# TOP.net
KiCad netlist of a schematic drawn in Altium Designer
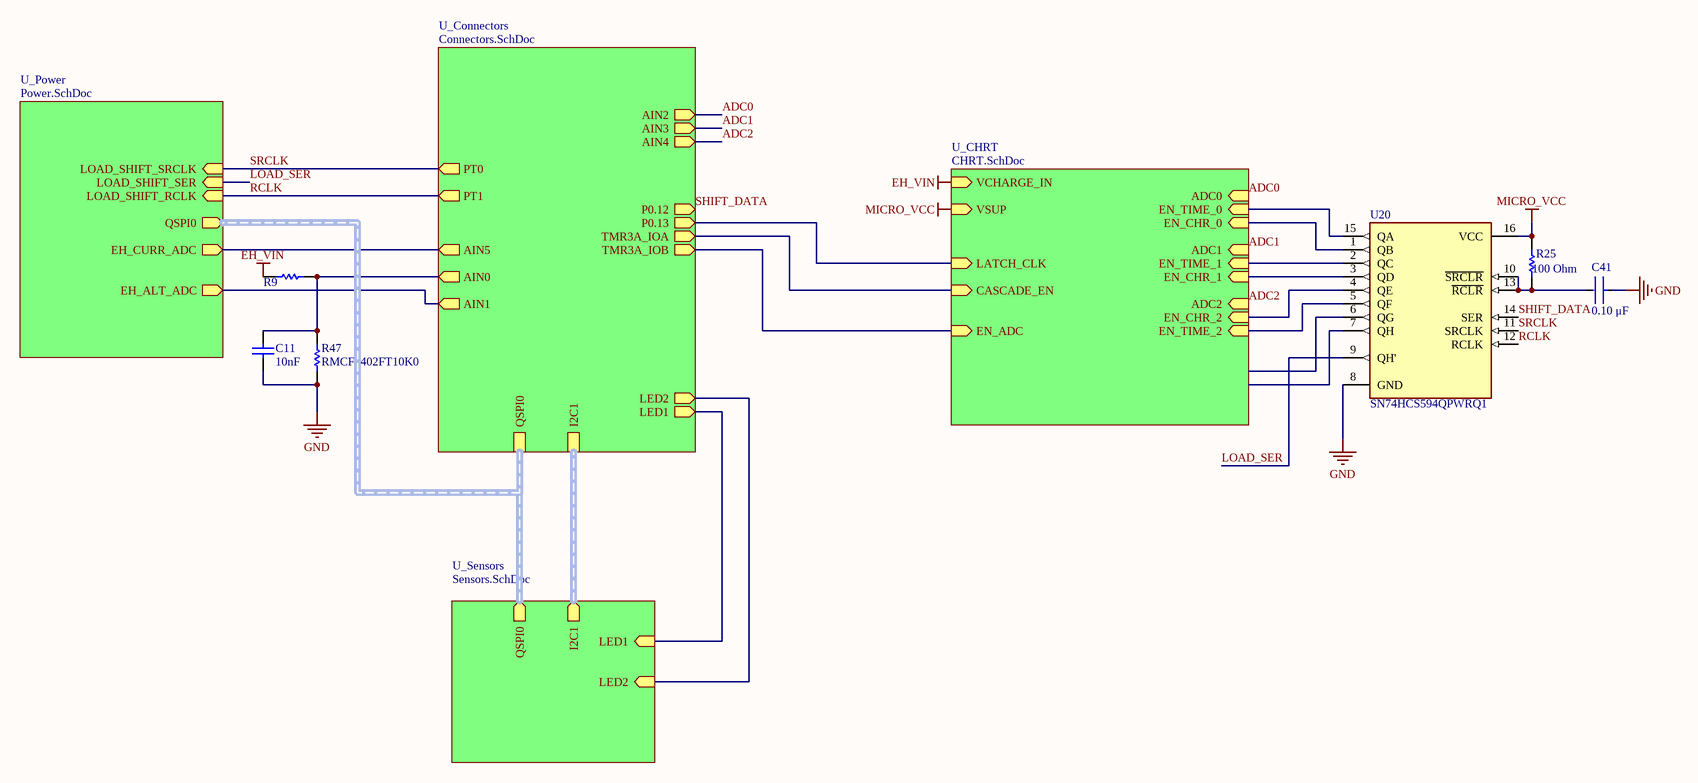
[diagram p0: TOP.SchDoc]

(export (version "E")
  (design (tool "Eeschema 10.0.6"))
  (components
    (comp (ref "C11")
      (value "GRM188R71H103KA01D")
      (footprint "CAPC1608X90X35ML10T15")
      (description "Chip Capacitor, 10 nF, +/- 10%, 50 V, -55 to 125 degC, 0603 (1608 Metric), RoHS, Tape and Reel")
      (fields
        (field (name "VOLTAGE") "50V")
        (field (name "TOLERANCE") "10%")
        (field (name "CAPACITANCE") "10nF")
      )
      (libsource (lib "Altium Content Vault") (part "CAP-NP-2"))
    )
    (comp (ref "C41")
      (value "C0402C104K8PACTU")
      (footprint "FP-C0402-BB-MFG")
      (description "CAP CER 0.1UF 10V X5R 0402")
      (fields
        (field (name "CAPACITANCE") "0.10 μF")
        (field (name "MANUFACTURER") "Kemet")
        (field (name "TOLERANCE") "0.1")
      )
      (libsource (lib "Altium Content Vault") (part "b4654b650e69147ec39a6b967a45e02"))
    )
    (comp (ref "R9")
      (value "RC0402JR-075M6L")
      (footprint "RESC1005X40X25ML05T10")
      (fields (field (name "MANUFACTURER") "Yageo / Phycomp"))
      (libsource (lib "Altium Content Vault") (part "RES"))
    )
    (comp (ref "R25")
      (value "ERJ-2RKF1000X")
      (footprint "RESC1005X40X25LL05T05")
      (description "Chip Resistor, 100 Ohm, +/- 1%, 100 mW, -55 to 155 degC, 0402 (1005 Metric), RoHS, Tape and Reel")
      (fields
        (field (name "MANUFACTURER") "Basic Passives")
        (field (name "TOLERANCE") "1%")
        (field (name "RESISTANCE") "100 Ohm")
      )
      (libsource (lib "Altium Content Vault") (part "RES-2"))
    )
    (comp (ref "R47")
      (value "RMCF0402FT10K0")
      (footprint "RESC1005X40X25ML05T10")
      (fields (field (name "MANUFACTURER") "Yageo / Phycomp") (field (name "PART NUMBER") "RC0402FR-071ML"))
      (libsource (lib "Altium Content Vault") (part "RES"))
    )
    (comp (ref "U20")
      (value "SN74HCS594QPWRQ1")
      (footprint "FP-PW0016A-IPC_A")
      (description "AUTOMOTIVE 8-BIT SHIFT REGISTERS")
      (libsource (lib "Altium Content Vault") (part "ee4c9120f52ff91501c7aa2bff67eb2"))
    )
  )
  (nets
    (net (code "4") (name "/AIN0") (class "Default")
      (node (ref "C11") (pin "2") (pinfunction "2_2") (pintype "passive"))
      (node (ref "R47") (pin "2") (pinfunction "2_2") (pintype "passive"))
      (node (ref "R9") (pin "2") (pinfunction "2_2") (pintype "passive"))
    )
    (net (code "7") (name "/EN_CHR_0") (class "Default")
      (node (ref "U20") (pin "1") (pinfunction "QB_1") (pintype "output"))
    )
    (net (code "8") (name "/EN_CHR_1") (class "Default")
      (node (ref "U20") (pin "3") (pinfunction "QD_3") (pintype "output"))
    )
    (net (code "9") (name "/EN_CHR_2") (class "Default")
      (node (ref "U20") (pin "4") (pinfunction "QE_4") (pintype "output"))
    )
    (net (code "10") (name "/EN_TIME_0") (class "Default")
      (node (ref "U20") (pin "15") (pinfunction "QA_15") (pintype "output"))
    )
    (net (code "11") (name "/EN_TIME_1") (class "Default")
      (node (ref "U20") (pin "2") (pinfunction "QC_2") (pintype "output"))
    )
    (net (code "12") (name "/EN_TIME_2") (class "Default")
      (node (ref "U20") (pin "5") (pinfunction "QF_5") (pintype "output"))
    )
    (net (code "16") (name "/LOAD_SER") (class "Default")
      (node (ref "U20") (pin "9") (pinfunction "QH'_9") (pintype "output"))
    )
    (net (code "19") (name "/RCLK") (class "Default")
      (node (ref "U20") (pin "12") (pinfunction "RCLK_12") (pintype "input"))
    )
    (net (code "20") (name "/SHIFT_DATA") (class "Default")
      (node (ref "U20") (pin "14") (pinfunction "SER_14") (pintype "input"))
    )
    (net (code "21") (name "/SRCLK") (class "Default")
      (node (ref "U20") (pin "11") (pinfunction "SRCLK_11") (pintype "input"))
    )
    (net (code "24") (name "EH_VIN") (class "Default")
      (node (ref "R9") (pin "1") (pinfunction "1_1") (pintype "passive"))
    )
    (net (code "25") (name "GND") (class "Default")
      (node (ref "C11") (pin "1") (pinfunction "1_1") (pintype "passive"))
      (node (ref "C41") (pin "1") (pinfunction "1_1") (pintype "passive"))
      (node (ref "R47") (pin "1") (pinfunction "1_1") (pintype "passive"))
      (node (ref "U20") (pin "8") (pinfunction "GND_8") (pintype "power_in"))
    )
    (net (code "26") (name "MICRO_VCC") (class "Default")
      (node (ref "R25") (pin "2") (pinfunction "2_2") (pintype "passive"))
      (node (ref "U20") (pin "16") (pinfunction "VCC_16") (pintype "power_in"))
    )
    (net (code "27") (name "Net-(U20-~{RCLR})") (class "Default")
      (node (ref "C41") (pin "2") (pinfunction "2_2") (pintype "passive"))
      (node (ref "R25") (pin "1") (pinfunction "1_1") (pintype "passive"))
      (node (ref "U20") (pin "10") (pinfunction "~{SRCLR}_10") (pintype "input"))
      (node (ref "U20") (pin "13") (pinfunction "~{RCLR}_13") (pintype "input"))
    )
    (net (code "28") (name "unconnected-(U20-QG-Pad6)") (class "Default")
      (node (ref "U20") (pin "6") (pinfunction "QG_6") (pintype "output"))
    )
    (net (code "29") (name "unconnected-(U20-QH-Pad7)") (class "Default")
      (node (ref "U20") (pin "7") (pinfunction "QH_7") (pintype "output"))
    )
  )
)
